# buck_converters.net
KiCad netlist of a schematic drawn in EAGLE
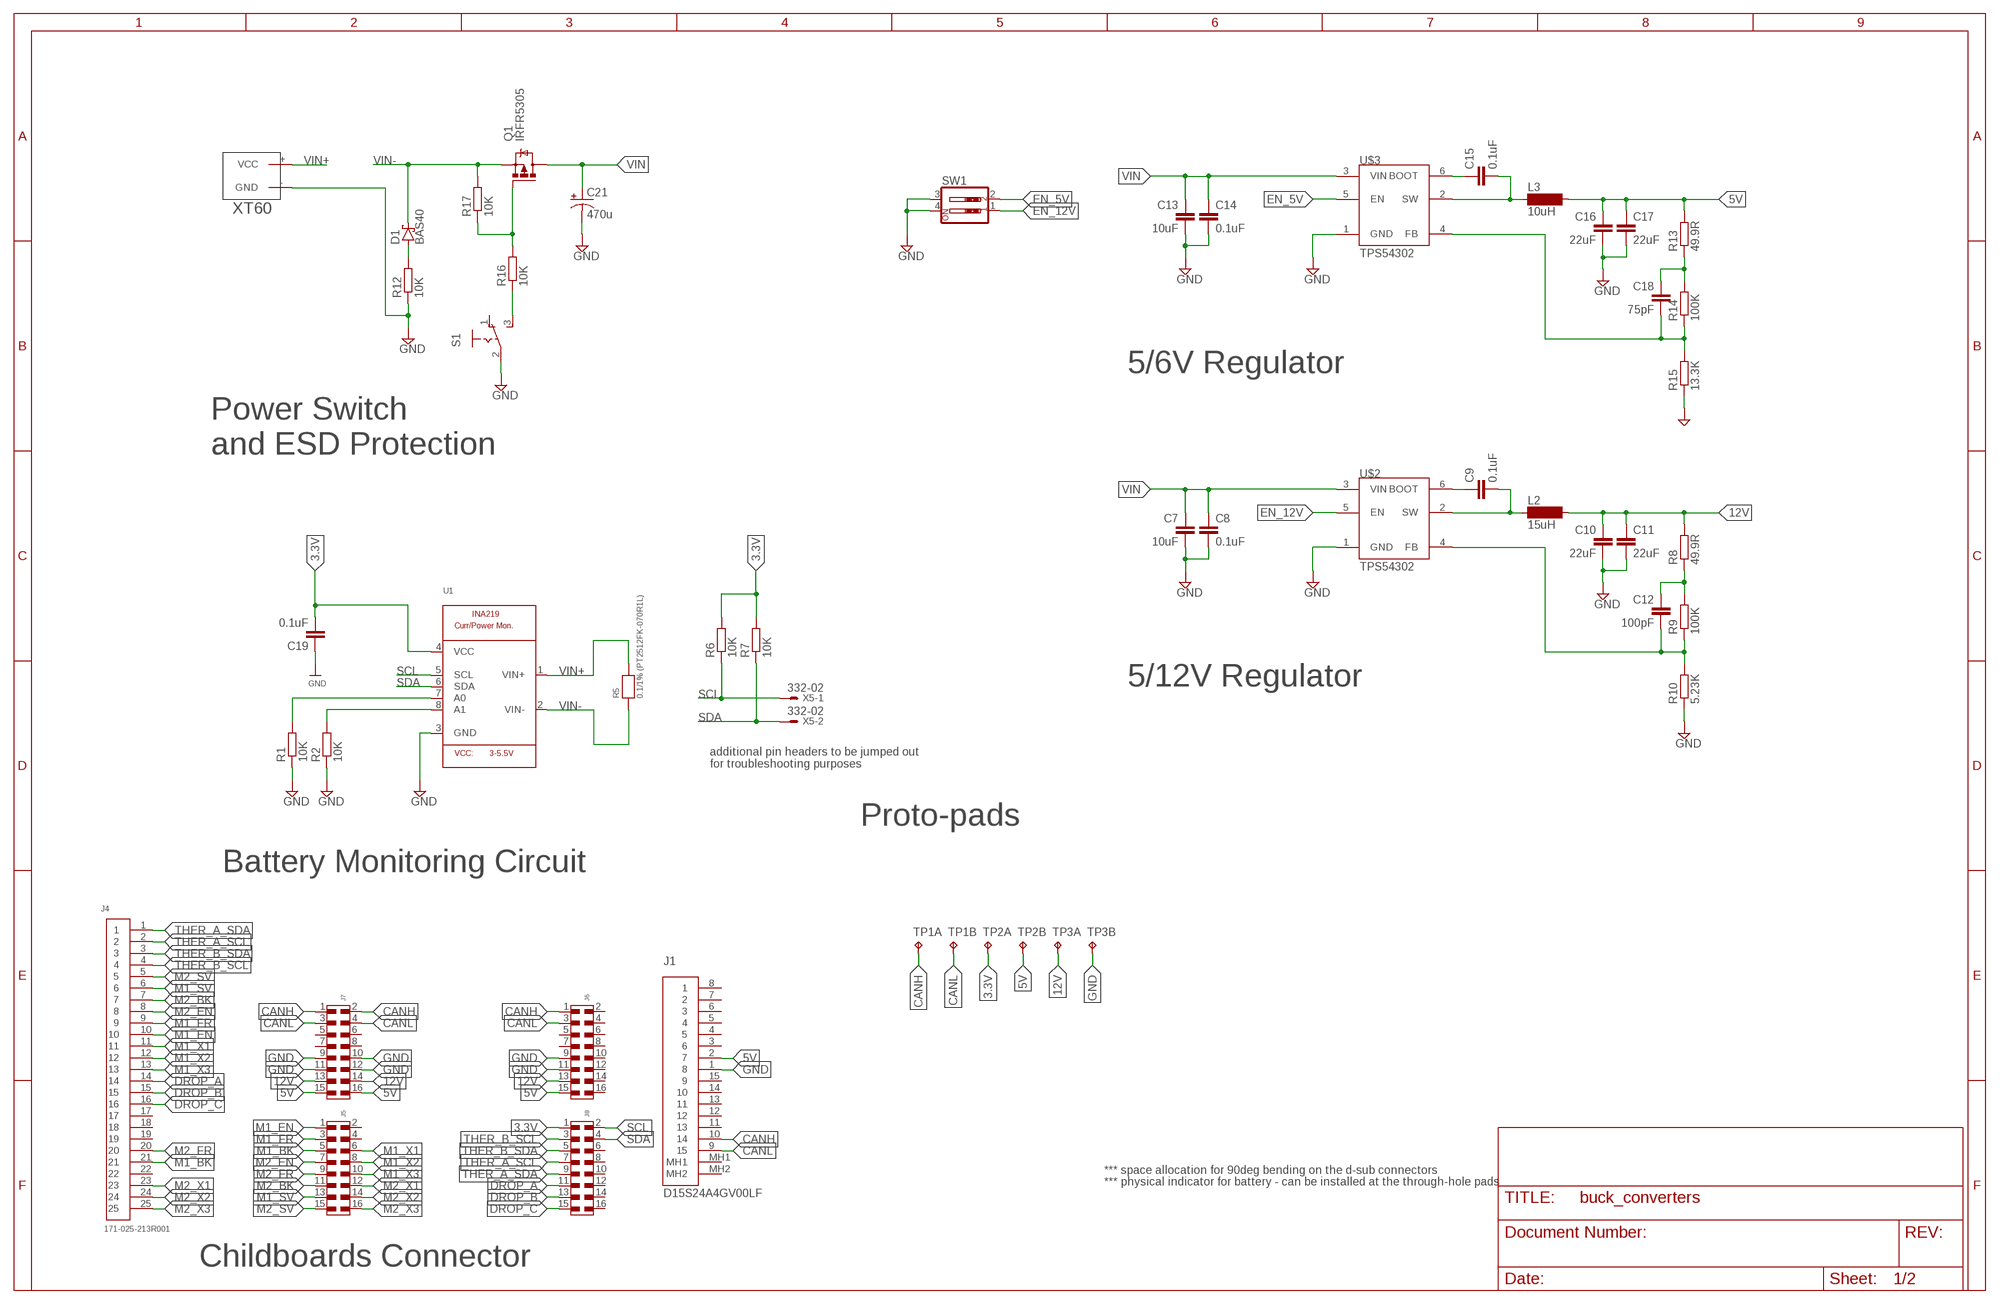
[diagram p0: schematic, sheet 1]
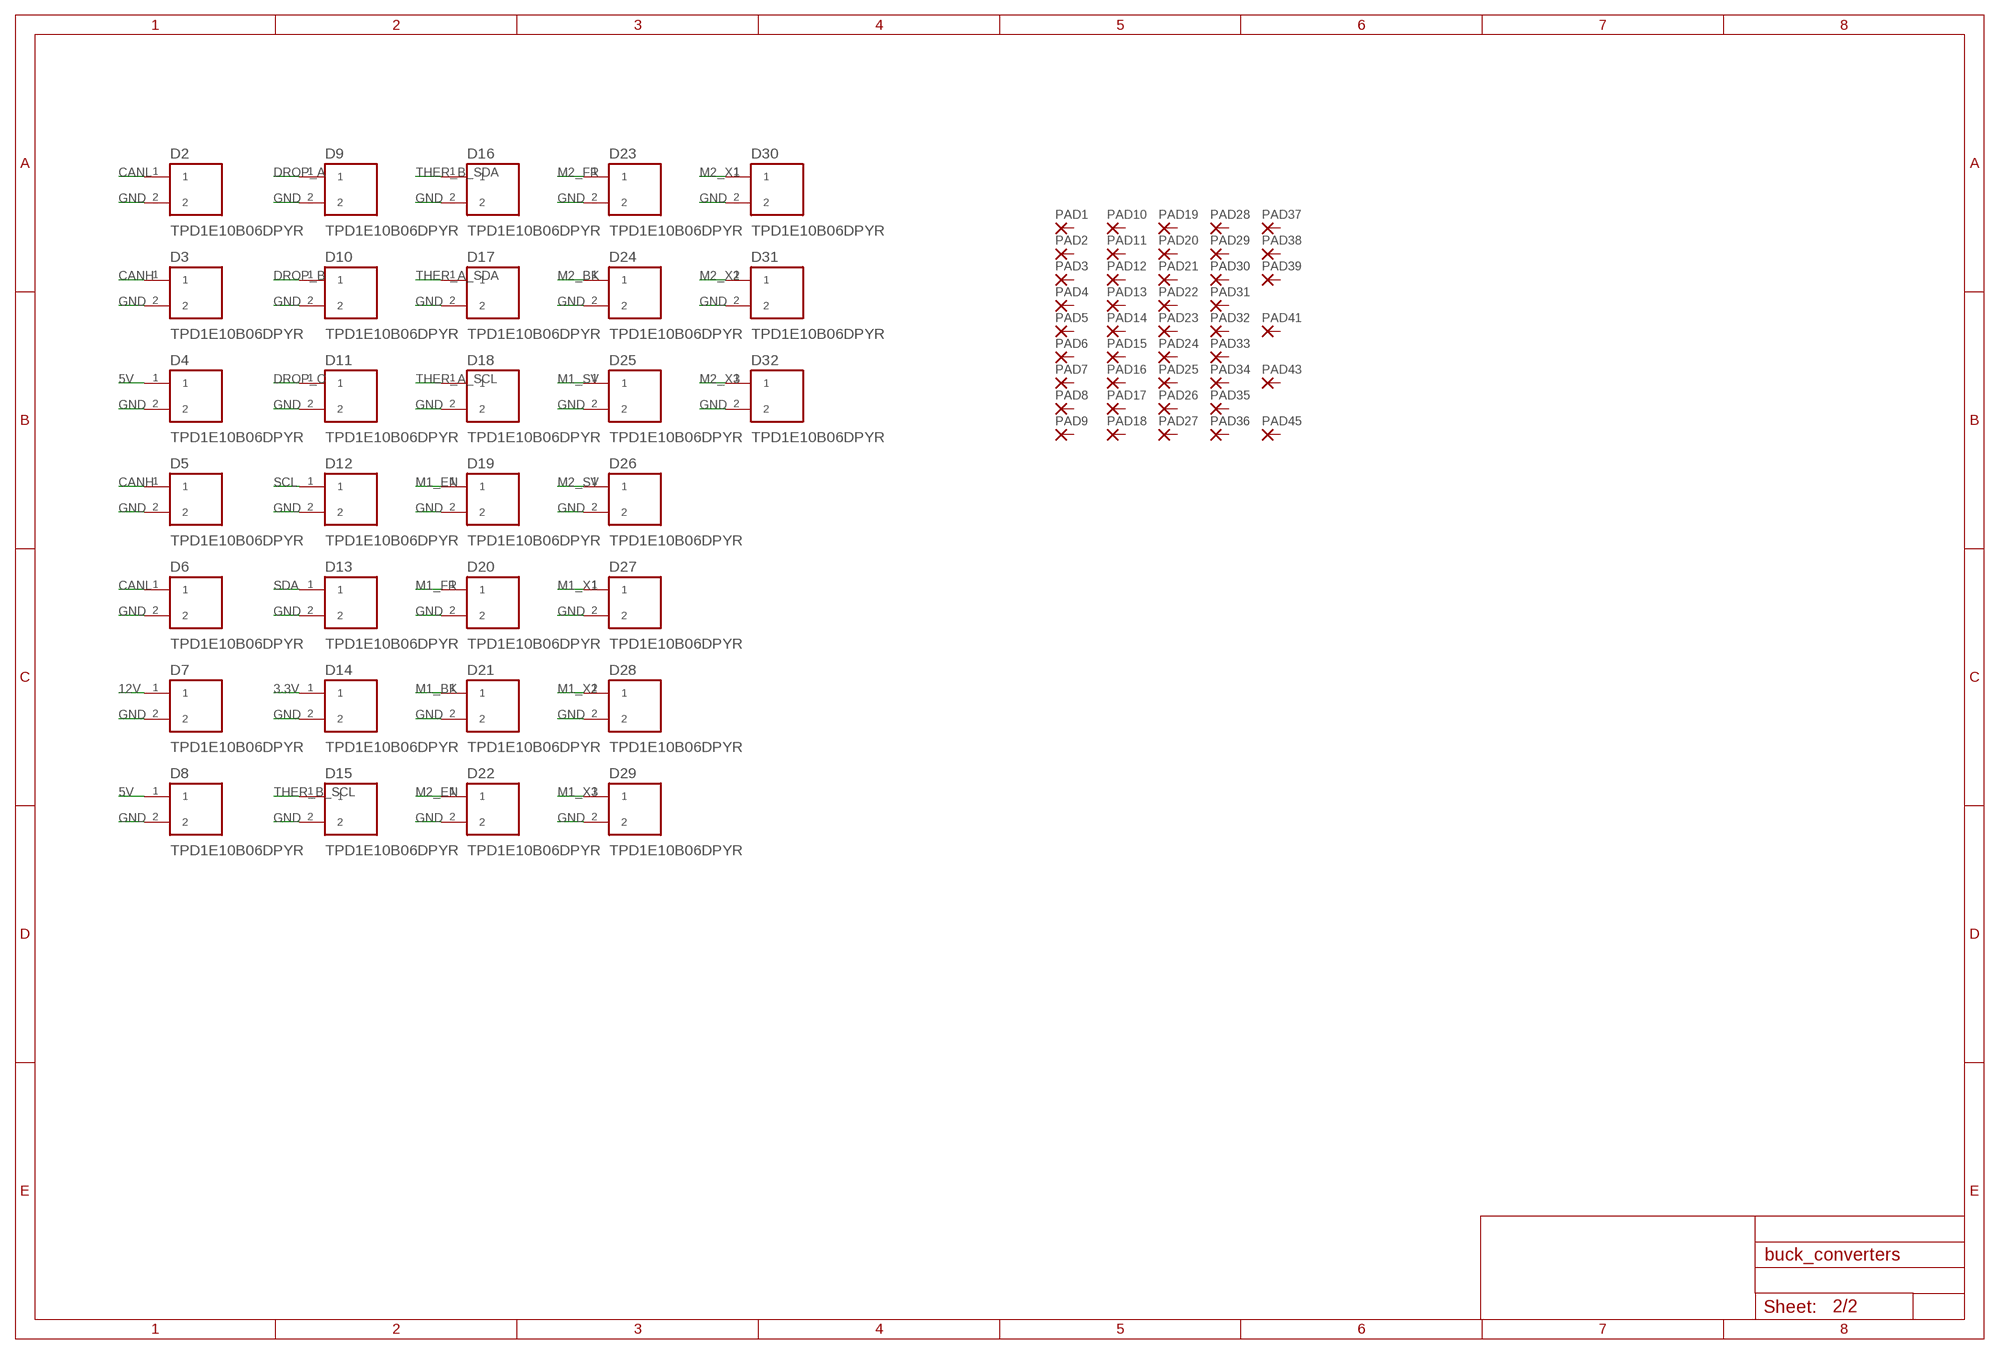
[diagram p1: schematic, sheet 2]

(export (version "E")
  (design (tool "Eeschema 10.0.6"))
  (components
    (comp (ref "C7")
      (value "10uF")
      (footprint "eagle-import:C0805")
      (libsource (lib "eagle-import") (part "C-EUC0805"))
    )
    (comp (ref "C8")
      (value "0.1uF")
      (footprint "eagle-import:C0805")
      (libsource (lib "eagle-import") (part "C-EUC0805"))
    )
    (comp (ref "C9")
      (value "0.1uF")
      (footprint "eagle-import:C0805")
      (libsource (lib "eagle-import") (part "C-EUC0805"))
    )
    (comp (ref "C10")
      (value "22uF")
      (footprint "eagle-import:C0805")
      (libsource (lib "eagle-import") (part "C-EUC0805"))
    )
    (comp (ref "C11")
      (value "22uF")
      (footprint "eagle-import:C0805")
      (libsource (lib "eagle-import") (part "C-EUC0805"))
    )
    (comp (ref "C12")
      (value "100pF")
      (footprint "eagle-import:C0805")
      (libsource (lib "eagle-import") (part "C-EUC0805"))
    )
    (comp (ref "C13")
      (value "10uF")
      (footprint "eagle-import:C0805")
      (libsource (lib "eagle-import") (part "C-EUC0805"))
    )
    (comp (ref "C14")
      (value "0.1uF")
      (footprint "eagle-import:C0805")
      (libsource (lib "eagle-import") (part "C-EUC0805"))
    )
    (comp (ref "C15")
      (value "0.1uF")
      (footprint "eagle-import:C0805")
      (libsource (lib "eagle-import") (part "C-EUC0805"))
    )
    (comp (ref "C16")
      (value "22uF")
      (footprint "eagle-import:C0805")
      (libsource (lib "eagle-import") (part "C-EUC0805"))
    )
    (comp (ref "C17")
      (value "22uF")
      (footprint "eagle-import:C0805")
      (libsource (lib "eagle-import") (part "C-EUC0805"))
    )
    (comp (ref "C18")
      (value "75pF")
      (footprint "eagle-import:C0805")
      (libsource (lib "eagle-import") (part "C-EUC0805"))
    )
    (comp (ref "C19")
      (value "0.1uF")
      (footprint "eagle-import:C0805")
      (libsource (lib "eagle-import") (part "C-EUC0805"))
    )
    (comp (ref "C21")
      (value "470u")
      (footprint "eagle-import:153CLV-1010")
      (libsource (lib "eagle-import") (part "CPOL-US153CLV-1010"))
    )
    (comp (ref "D1")
      (value "BAS40")
      (footprint "eagle-import:SOT23")
      (libsource (lib "eagle-import") (part "BAS40"))
    )
    (comp (ref "J1")
      (value "D15S24A4GV00LF")
      (footprint "eagle-import:D15S24A4GV00LF")
      (fields
        (field (name "DIGIKEY_PART_NUMBER") "609-1497-ND")
        (field (name "MANUFACTURER") "Amphenol ICC (FCI)")
        (field (name "CREATED_BY") "PCBLayout.com")
      )
      (libsource (lib "eagle-import") (part "D15S24A4GV00LF"))
    )
    (comp (ref "J4")
      (value "171-025-213R001")
      (footprint "eagle-import:171-025-213R001")
      (fields
        (field (name "DIGIKEY_PART_NO") "4225FE-ND")
        (field (name "MANUFACTURER") "NorComp Inc.")
        (field (name "CREATED_BY") "PCBLayout.com")
      )
      (libsource (lib "eagle-import") (part "171-025-213R001"))
    )
    (comp (ref "J5")
      (value "6120XX20621_61201620621")
      (footprint "eagle-import:61201620621")
      (libsource (lib "eagle-import") (part "6120XX20621_61201620621"))
    )
    (comp (ref "J6")
      (value "6120XX20621_61201620621")
      (footprint "eagle-import:61201620621")
      (libsource (lib "eagle-import") (part "6120XX20621_61201620621"))
    )
    (comp (ref "J7")
      (value "6123XX20621_61231620621")
      (footprint "eagle-import:61231620621")
      (libsource (lib "eagle-import") (part "6123XX20621_61231620621"))
    )
    (comp (ref "J8")
      (value "6120XX20621_61201620621")
      (footprint "eagle-import:61201620621")
      (libsource (lib "eagle-import") (part "6120XX20621_61201620621"))
    )
    (comp (ref "L2")
      (value "15uH")
      (footprint "eagle-import:SM-NE29")
      (libsource (lib "eagle-import") (part "SM-NE29"))
    )
    (comp (ref "L3")
      (value "10uH")
      (footprint "eagle-import:SM-NE29")
      (libsource (lib "eagle-import") (part "SM-NE29"))
    )
    (comp (ref "Q1")
      (value "IRFR5305")
      (footprint "eagle-import:D-PAK_TO252AA")
      (libsource (lib "eagle-import") (part "IRF?5305R"))
    )
    (comp (ref "R1")
      (value "10K")
      (footprint "eagle-import:R0805")
      (libsource (lib "eagle-import") (part "R-EU_R0805"))
    )
    (comp (ref "R2")
      (value "10K")
      (footprint "eagle-import:R0805")
      (libsource (lib "eagle-import") (part "R-EU_R0805"))
    )
    (comp (ref "R5")
      (value "0.1/1% (PT2512FK-070R1L)")
      (footprint "eagle-import:2512")
      (libsource (lib "eagle-import") (part "RESISTOR2512"))
    )
    (comp (ref "R6")
      (value "10K")
      (footprint "eagle-import:R0805")
      (libsource (lib "eagle-import") (part "R-EU_R0805"))
    )
    (comp (ref "R7")
      (value "10K")
      (footprint "eagle-import:R0805")
      (libsource (lib "eagle-import") (part "R-EU_R0805"))
    )
    (comp (ref "R8")
      (value "49.9R")
      (footprint "eagle-import:R0805")
      (libsource (lib "eagle-import") (part "R-EU_R0805"))
    )
    (comp (ref "R9")
      (value "100K")
      (footprint "eagle-import:R0805")
      (libsource (lib "eagle-import") (part "R-EU_R0805"))
    )
    (comp (ref "R10")
      (value "5.23K")
      (footprint "eagle-import:R0805")
      (libsource (lib "eagle-import") (part "R-EU_R0805"))
    )
    (comp (ref "R12")
      (value "10K")
      (footprint "eagle-import:R0805")
      (libsource (lib "eagle-import") (part "R-EU_R0805"))
    )
    (comp (ref "R13")
      (value "49.9R")
      (footprint "eagle-import:R0805")
      (libsource (lib "eagle-import") (part "R-EU_R0805"))
    )
    (comp (ref "R14")
      (value "100K")
      (footprint "eagle-import:R0805")
      (libsource (lib "eagle-import") (part "R-EU_R0805"))
    )
    (comp (ref "R15")
      (value "13.3K")
      (footprint "eagle-import:R0805")
      (libsource (lib "eagle-import") (part "R-EU_R0805"))
    )
    (comp (ref "R16")
      (value "10K")
      (footprint "eagle-import:R0805")
      (libsource (lib "eagle-import") (part "R-EU_R0805"))
    )
    (comp (ref "R17")
      (value "10K")
      (footprint "eagle-import:R0805")
      (libsource (lib "eagle-import") (part "R-EU_R0805"))
    )
    (comp (ref "S1")
      (value "255SB")
      (footprint "eagle-import:255SB")
      (libsource (lib "eagle-import") (part "255SB"))
    )
    (comp (ref "SW1")
      (value "SW_DIP-2")
      (footprint "eagle-import:EDG-02")
      (libsource (lib "eagle-import") (part "SW_DIP-2"))
    )
    (comp (ref "TP1")
      (value "TP2P2-38-17")
      (footprint "eagle-import:P2-38-17")
      (libsource (lib "eagle-import") (part "TP2P2-38-17"))
    )
    (comp (ref "TP2")
      (value "TP2P2-38-17")
      (footprint "eagle-import:P2-38-17")
      (libsource (lib "eagle-import") (part "TP2P2-38-17"))
    )
    (comp (ref "TP3")
      (value "TP2P2-38-17")
      (footprint "eagle-import:P2-38-17")
      (libsource (lib "eagle-import") (part "TP2P2-38-17"))
    )
    (comp (ref "U$2")
      (value "TPS54302")
      (footprint "eagle-import:SOT23-6")
      (libsource (lib "eagle-import") (part "TPS54302"))
    )
    (comp (ref "U$3")
      (value "TPS54302")
      (footprint "eagle-import:SOT23-6")
      (libsource (lib "eagle-import") (part "TPS54302"))
    )
    (comp (ref "U$9")
      (value "XT60")
      (footprint "eagle-import:XT60")
      (libsource (lib "eagle-import") (part "XT60"))
    )
    (comp (ref "U1")
      (value "INA219")
      (footprint "eagle-import:SOT23-8")
      (libsource (lib "eagle-import") (part "INA219"))
    )
    (comp (ref "X5")
      (value "332-02")
      (footprint "eagle-import:332-02")
      (libsource (lib "eagle-import") (part "332-02"))
    )
    (comp (ref "D2")
      (value "TPD1E10B06DPYR")
      (footprint "eagle-import:DIO_TPD1E05U06DPYR")
      (fields (field (name "MF") "Texas Instruments"))
      (libsource (lib "eagle-import") (part "TPD1E10B06DPYR"))
    )
    (comp (ref "D3")
      (value "TPD1E10B06DPYR")
      (footprint "eagle-import:DIO_TPD1E05U06DPYR")
      (fields (field (name "MF") "Texas Instruments"))
      (libsource (lib "eagle-import") (part "TPD1E10B06DPYR"))
    )
    (comp (ref "D4")
      (value "TPD1E10B06DPYR")
      (footprint "eagle-import:DIO_TPD1E05U06DPYR")
      (fields (field (name "MF") "Texas Instruments"))
      (libsource (lib "eagle-import") (part "TPD1E10B06DPYR"))
    )
    (comp (ref "D5")
      (value "TPD1E10B06DPYR")
      (footprint "eagle-import:DIO_TPD1E05U06DPYR")
      (fields (field (name "MF") "Texas Instruments"))
      (libsource (lib "eagle-import") (part "TPD1E10B06DPYR"))
    )
    (comp (ref "D6")
      (value "TPD1E10B06DPYR")
      (footprint "eagle-import:DIO_TPD1E05U06DPYR")
      (fields (field (name "MF") "Texas Instruments"))
      (libsource (lib "eagle-import") (part "TPD1E10B06DPYR"))
    )
    (comp (ref "D7")
      (value "TPD1E10B06DPYR")
      (footprint "eagle-import:DIO_TPD1E05U06DPYR")
      (fields (field (name "MF") "Texas Instruments"))
      (libsource (lib "eagle-import") (part "TPD1E10B06DPYR"))
    )
    (comp (ref "D8")
      (value "TPD1E10B06DPYR")
      (footprint "eagle-import:DIO_TPD1E05U06DPYR")
      (fields (field (name "MF") "Texas Instruments"))
      (libsource (lib "eagle-import") (part "TPD1E10B06DPYR"))
    )
    (comp (ref "D9")
      (value "TPD1E10B06DPYR")
      (footprint "eagle-import:DIO_TPD1E05U06DPYR")
      (fields (field (name "MF") "Texas Instruments"))
      (libsource (lib "eagle-import") (part "TPD1E10B06DPYR"))
    )
    (comp (ref "D10")
      (value "TPD1E10B06DPYR")
      (footprint "eagle-import:DIO_TPD1E05U06DPYR")
      (fields (field (name "MF") "Texas Instruments"))
      (libsource (lib "eagle-import") (part "TPD1E10B06DPYR"))
    )
    (comp (ref "D11")
      (value "TPD1E10B06DPYR")
      (footprint "eagle-import:DIO_TPD1E05U06DPYR")
      (fields (field (name "MF") "Texas Instruments"))
      (libsource (lib "eagle-import") (part "TPD1E10B06DPYR"))
    )
    (comp (ref "D12")
      (value "TPD1E10B06DPYR")
      (footprint "eagle-import:DIO_TPD1E05U06DPYR")
      (fields (field (name "MF") "Texas Instruments"))
      (libsource (lib "eagle-import") (part "TPD1E10B06DPYR"))
    )
    (comp (ref "D13")
      (value "TPD1E10B06DPYR")
      (footprint "eagle-import:DIO_TPD1E05U06DPYR")
      (fields (field (name "MF") "Texas Instruments"))
      (libsource (lib "eagle-import") (part "TPD1E10B06DPYR"))
    )
    (comp (ref "D14")
      (value "TPD1E10B06DPYR")
      (footprint "eagle-import:DIO_TPD1E05U06DPYR")
      (fields (field (name "MF") "Texas Instruments"))
      (libsource (lib "eagle-import") (part "TPD1E10B06DPYR"))
    )
    (comp (ref "D15")
      (value "TPD1E10B06DPYR")
      (footprint "eagle-import:DIO_TPD1E05U06DPYR")
      (fields (field (name "MF") "Texas Instruments"))
      (libsource (lib "eagle-import") (part "TPD1E10B06DPYR"))
    )
    (comp (ref "D16")
      (value "TPD1E10B06DPYR")
      (footprint "eagle-import:DIO_TPD1E05U06DPYR")
      (fields (field (name "MF") "Texas Instruments"))
      (libsource (lib "eagle-import") (part "TPD1E10B06DPYR"))
    )
    (comp (ref "D17")
      (value "TPD1E10B06DPYR")
      (footprint "eagle-import:DIO_TPD1E05U06DPYR")
      (fields (field (name "MF") "Texas Instruments"))
      (libsource (lib "eagle-import") (part "TPD1E10B06DPYR"))
    )
    (comp (ref "D18")
      (value "TPD1E10B06DPYR")
      (footprint "eagle-import:DIO_TPD1E05U06DPYR")
      (fields (field (name "MF") "Texas Instruments"))
      (libsource (lib "eagle-import") (part "TPD1E10B06DPYR"))
    )
    (comp (ref "D19")
      (value "TPD1E10B06DPYR")
      (footprint "eagle-import:DIO_TPD1E05U06DPYR")
      (fields (field (name "MF") "Texas Instruments"))
      (libsource (lib "eagle-import") (part "TPD1E10B06DPYR"))
    )
    (comp (ref "D20")
      (value "TPD1E10B06DPYR")
      (footprint "eagle-import:DIO_TPD1E05U06DPYR")
      (fields (field (name "MF") "Texas Instruments"))
      (libsource (lib "eagle-import") (part "TPD1E10B06DPYR"))
    )
    (comp (ref "D21")
      (value "TPD1E10B06DPYR")
      (footprint "eagle-import:DIO_TPD1E05U06DPYR")
      (fields (field (name "MF") "Texas Instruments"))
      (libsource (lib "eagle-import") (part "TPD1E10B06DPYR"))
    )
    (comp (ref "D22")
      (value "TPD1E10B06DPYR")
      (footprint "eagle-import:DIO_TPD1E05U06DPYR")
      (fields (field (name "MF") "Texas Instruments"))
      (libsource (lib "eagle-import") (part "TPD1E10B06DPYR"))
    )
    (comp (ref "D23")
      (value "TPD1E10B06DPYR")
      (footprint "eagle-import:DIO_TPD1E05U06DPYR")
      (fields (field (name "MF") "Texas Instruments"))
      (libsource (lib "eagle-import") (part "TPD1E10B06DPYR"))
    )
    (comp (ref "D24")
      (value "TPD1E10B06DPYR")
      (footprint "eagle-import:DIO_TPD1E05U06DPYR")
      (fields (field (name "MF") "Texas Instruments"))
      (libsource (lib "eagle-import") (part "TPD1E10B06DPYR"))
    )
    (comp (ref "D25")
      (value "TPD1E10B06DPYR")
      (footprint "eagle-import:DIO_TPD1E05U06DPYR")
      (fields (field (name "MF") "Texas Instruments"))
      (libsource (lib "eagle-import") (part "TPD1E10B06DPYR"))
    )
    (comp (ref "D26")
      (value "TPD1E10B06DPYR")
      (footprint "eagle-import:DIO_TPD1E05U06DPYR")
      (fields (field (name "MF") "Texas Instruments"))
      (libsource (lib "eagle-import") (part "TPD1E10B06DPYR"))
    )
    (comp (ref "D27")
      (value "TPD1E10B06DPYR")
      (footprint "eagle-import:DIO_TPD1E05U06DPYR")
      (fields (field (name "MF") "Texas Instruments"))
      (libsource (lib "eagle-import") (part "TPD1E10B06DPYR"))
    )
    (comp (ref "D28")
      (value "TPD1E10B06DPYR")
      (footprint "eagle-import:DIO_TPD1E05U06DPYR")
      (fields (field (name "MF") "Texas Instruments"))
      (libsource (lib "eagle-import") (part "TPD1E10B06DPYR"))
    )
    (comp (ref "D29")
      (value "TPD1E10B06DPYR")
      (footprint "eagle-import:DIO_TPD1E05U06DPYR")
      (fields (field (name "MF") "Texas Instruments"))
      (libsource (lib "eagle-import") (part "TPD1E10B06DPYR"))
    )
    (comp (ref "D30")
      (value "TPD1E10B06DPYR")
      (footprint "eagle-import:DIO_TPD1E05U06DPYR")
      (fields (field (name "MF") "Texas Instruments"))
      (libsource (lib "eagle-import") (part "TPD1E10B06DPYR"))
    )
    (comp (ref "D31")
      (value "TPD1E10B06DPYR")
      (footprint "eagle-import:DIO_TPD1E05U06DPYR")
      (fields (field (name "MF") "Texas Instruments"))
      (libsource (lib "eagle-import") (part "TPD1E10B06DPYR"))
    )
    (comp (ref "D32")
      (value "TPD1E10B06DPYR")
      (footprint "eagle-import:DIO_TPD1E05U06DPYR")
      (fields (field (name "MF") "Texas Instruments"))
      (libsource (lib "eagle-import") (part "TPD1E10B06DPYR"))
    )
    (comp (ref "PAD1")
      (value "2,54/1,1")
      (footprint "eagle-import:2,54_1,1")
      (libsource (lib "eagle-import") (part "2,54/1,1"))
    )
    (comp (ref "PAD2")
      (value "2,54/1,1")
      (footprint "eagle-import:2,54_1,1")
      (libsource (lib "eagle-import") (part "2,54/1,1"))
    )
    (comp (ref "PAD3")
      (value "2,54/1,1")
      (footprint "eagle-import:2,54_1,1")
      (libsource (lib "eagle-import") (part "2,54/1,1"))
    )
    (comp (ref "PAD4")
      (value "2,54/1,1")
      (footprint "eagle-import:2,54_1,1")
      (libsource (lib "eagle-import") (part "2,54/1,1"))
    )
    (comp (ref "PAD5")
      (value "2,54/1,1")
      (footprint "eagle-import:2,54_1,1")
      (libsource (lib "eagle-import") (part "2,54/1,1"))
    )
    (comp (ref "PAD6")
      (value "2,54/1,1")
      (footprint "eagle-import:2,54_1,1")
      (libsource (lib "eagle-import") (part "2,54/1,1"))
    )
    (comp (ref "PAD7")
      (value "2,54/1,1")
      (footprint "eagle-import:2,54_1,1")
      (libsource (lib "eagle-import") (part "2,54/1,1"))
    )
    (comp (ref "PAD8")
      (value "2,54/1,1")
      (footprint "eagle-import:2,54_1,1")
      (libsource (lib "eagle-import") (part "2,54/1,1"))
    )
    (comp (ref "PAD9")
      (value "2,54/1,1")
      (footprint "eagle-import:2,54_1,1")
      (libsource (lib "eagle-import") (part "2,54/1,1"))
    )
    (comp (ref "PAD10")
      (value "2,54/1,1")
      (footprint "eagle-import:2,54_1,1")
      (libsource (lib "eagle-import") (part "2,54/1,1"))
    )
    (comp (ref "PAD11")
      (value "2,54/1,1")
      (footprint "eagle-import:2,54_1,1")
      (libsource (lib "eagle-import") (part "2,54/1,1"))
    )
    (comp (ref "PAD12")
      (value "2,54/1,1")
      (footprint "eagle-import:2,54_1,1")
      (libsource (lib "eagle-import") (part "2,54/1,1"))
    )
    (comp (ref "PAD13")
      (value "2,54/1,1")
      (footprint "eagle-import:2,54_1,1")
      (libsource (lib "eagle-import") (part "2,54/1,1"))
    )
    (comp (ref "PAD14")
      (value "2,54/1,1")
      (footprint "eagle-import:2,54_1,1")
      (libsource (lib "eagle-import") (part "2,54/1,1"))
    )
    (comp (ref "PAD15")
      (value "2,54/1,1")
      (footprint "eagle-import:2,54_1,1")
      (libsource (lib "eagle-import") (part "2,54/1,1"))
    )
    (comp (ref "PAD16")
      (value "2,54/1,1")
      (footprint "eagle-import:2,54_1,1")
      (libsource (lib "eagle-import") (part "2,54/1,1"))
    )
    (comp (ref "PAD17")
      (value "2,54/1,1")
      (footprint "eagle-import:2,54_1,1")
      (libsource (lib "eagle-import") (part "2,54/1,1"))
    )
    (comp (ref "PAD18")
      (value "2,54/1,1")
      (footprint "eagle-import:2,54_1,1")
      (libsource (lib "eagle-import") (part "2,54/1,1"))
    )
    (comp (ref "PAD19")
      (value "2,54/1,1")
      (footprint "eagle-import:2,54_1,1")
      (libsource (lib "eagle-import") (part "2,54/1,1"))
    )
    (comp (ref "PAD20")
      (value "2,54/1,1")
      (footprint "eagle-import:2,54_1,1")
      (libsource (lib "eagle-import") (part "2,54/1,1"))
    )
    (comp (ref "PAD21")
      (value "2,54/1,1")
      (footprint "eagle-import:2,54_1,1")
      (libsource (lib "eagle-import") (part "2,54/1,1"))
    )
    (comp (ref "PAD22")
      (value "2,54/1,1")
      (footprint "eagle-import:2,54_1,1")
      (libsource (lib "eagle-import") (part "2,54/1,1"))
    )
    (comp (ref "PAD23")
      (value "2,54/1,1")
      (footprint "eagle-import:2,54_1,1")
      (libsource (lib "eagle-import") (part "2,54/1,1"))
    )
    (comp (ref "PAD24")
      (value "2,54/1,1")
      (footprint "eagle-import:2,54_1,1")
      (libsource (lib "eagle-import") (part "2,54/1,1"))
    )
    (comp (ref "PAD25")
      (value "2,54/1,1")
      (footprint "eagle-import:2,54_1,1")
      (libsource (lib "eagle-import") (part "2,54/1,1"))
    )
    (comp (ref "PAD26")
      (value "2,54/1,1")
      (footprint "eagle-import:2,54_1,1")
      (libsource (lib "eagle-import") (part "2,54/1,1"))
    )
    (comp (ref "PAD27")
      (value "2,54/1,1")
      (footprint "eagle-import:2,54_1,1")
      (libsource (lib "eagle-import") (part "2,54/1,1"))
    )
    (comp (ref "PAD28")
      (value "2,54/1,1")
      (footprint "eagle-import:2,54_1,1")
      (libsource (lib "eagle-import") (part "2,54/1,1"))
    )
    (comp (ref "PAD29")
      (value "2,54/1,1")
      (footprint "eagle-import:2,54_1,1")
      (libsource (lib "eagle-import") (part "2,54/1,1"))
    )
    (comp (ref "PAD30")
      (value "2,54/1,1")
      (footprint "eagle-import:2,54_1,1")
      (libsource (lib "eagle-import") (part "2,54/1,1"))
    )
    (comp (ref "PAD31")
      (value "2,54/1,1")
      (footprint "eagle-import:2,54_1,1")
      (libsource (lib "eagle-import") (part "2,54/1,1"))
    )
    (comp (ref "PAD32")
      (value "2,54/1,1")
      (footprint "eagle-import:2,54_1,1")
      (libsource (lib "eagle-import") (part "2,54/1,1"))
    )
    (comp (ref "PAD33")
      (value "2,54/1,1")
      (footprint "eagle-import:2,54_1,1")
      (libsource (lib "eagle-import") (part "2,54/1,1"))
    )
    (comp (ref "PAD34")
      (value "2,54/1,1")
      (footprint "eagle-import:2,54_1,1")
      (libsource (lib "eagle-import") (part "2,54/1,1"))
    )
    (comp (ref "PAD35")
      (value "2,54/1,1")
      (footprint "eagle-import:2,54_1,1")
      (libsource (lib "eagle-import") (part "2,54/1,1"))
    )
    (comp (ref "PAD36")
      (value "2,54/1,1")
      (footprint "eagle-import:2,54_1,1")
      (libsource (lib "eagle-import") (part "2,54/1,1"))
    )
    (comp (ref "PAD37")
      (value "2,54/1,1")
      (footprint "eagle-import:2,54_1,1")
      (libsource (lib "eagle-import") (part "2,54/1,1"))
    )
    (comp (ref "PAD38")
      (value "2,54/1,1")
      (footprint "eagle-import:2,54_1,1")
      (libsource (lib "eagle-import") (part "2,54/1,1"))
    )
    (comp (ref "PAD39")
      (value "2,54/1,1")
      (footprint "eagle-import:2,54_1,1")
      (libsource (lib "eagle-import") (part "2,54/1,1"))
    )
    (comp (ref "PAD41")
      (value "2,54/1,1")
      (footprint "eagle-import:2,54_1,1")
      (libsource (lib "eagle-import") (part "2,54/1,1"))
    )
    (comp (ref "PAD43")
      (value "2,54/1,1")
      (footprint "eagle-import:2,54_1,1")
      (libsource (lib "eagle-import") (part "2,54/1,1"))
    )
    (comp (ref "PAD45")
      (value "2,54/1,1")
      (footprint "eagle-import:2,54_1,1")
      (libsource (lib "eagle-import") (part "2,54/1,1"))
    )
  )
  (nets
    (net (code "1") (name "3.3V") (class "Default")
      (node (ref "C19") (pin "2") (pinfunction "2_2") (pintype "passive"))
      (node (ref "D14") (pin "1") (pinfunction "1_1") (pintype "bidirectional"))
      (node (ref "J8") (pin "1") (pinfunction "1_1") (pintype "passive"))
      (node (ref "R6") (pin "2") (pinfunction "2_2") (pintype "passive"))
      (node (ref "R7") (pin "2") (pinfunction "2_2") (pintype "passive"))
      (node (ref "TP2") (pin "TP-1") (pinfunction "TP_TP-1") (pintype "input"))
      (node (ref "U1") (pin "4") (pinfunction "VCC_4") (pintype "bidirectional"))
    )
    (net (code "2") (name "5V") (class "Default")
      (node (ref "C16") (pin "1") (pinfunction "1_1") (pintype "passive"))
      (node (ref "C17") (pin "1") (pinfunction "1_1") (pintype "passive"))
      (node (ref "D4") (pin "1") (pinfunction "1_1") (pintype "bidirectional"))
      (node (ref "D8") (pin "1") (pinfunction "1_1") (pintype "bidirectional"))
      (node (ref "J1") (pin "2") (pinfunction "7_2") (pintype "passive"))
      (node (ref "J6") (pin "15") (pinfunction "15_15") (pintype "passive"))
      (node (ref "J7") (pin "15") (pinfunction "15_15") (pintype "passive"))
      (node (ref "J7") (pin "16") (pinfunction "16_16") (pintype "passive"))
      (node (ref "L3") (pin "2") (pinfunction "2_2") (pintype "passive"))
      (node (ref "R13") (pin "2") (pinfunction "2_2") (pintype "passive"))
      (node (ref "TP2") (pin "TP-2") (pinfunction "TP_TP-2") (pintype "input"))
    )
    (net (code "3") (name "12V") (class "Default")
      (node (ref "C10") (pin "1") (pinfunction "1_1") (pintype "passive"))
      (node (ref "C11") (pin "1") (pinfunction "1_1") (pintype "passive"))
      (node (ref "D7") (pin "1") (pinfunction "1_1") (pintype "bidirectional"))
      (node (ref "J6") (pin "13") (pinfunction "13_13") (pintype "passive"))
      (node (ref "J7") (pin "13") (pinfunction "13_13") (pintype "passive"))
      (node (ref "J7") (pin "14") (pinfunction "14_14") (pintype "passive"))
      (node (ref "L2") (pin "2") (pinfunction "2_2") (pintype "passive"))
      (node (ref "R8") (pin "2") (pinfunction "2_2") (pintype "passive"))
      (node (ref "TP3") (pin "TP-1") (pinfunction "TP_TP-1") (pintype "input"))
    )
    (net (code "4") (name "CANH") (class "Default")
      (node (ref "D3") (pin "1") (pinfunction "1_1") (pintype "bidirectional"))
      (node (ref "D5") (pin "1") (pinfunction "1_1") (pintype "bidirectional"))
      (node (ref "J1") (pin "10") (pinfunction "14_10") (pintype "passive"))
      (node (ref "J6") (pin "1") (pinfunction "1_1") (pintype "passive"))
      (node (ref "J7") (pin "1") (pinfunction "1_1") (pintype "passive"))
      (node (ref "J7") (pin "2") (pinfunction "2_2") (pintype "passive"))
      (node (ref "TP1") (pin "TP-1") (pinfunction "TP_TP-1") (pintype "input"))
    )
    (net (code "5") (name "CANL") (class "Default")
      (node (ref "D2") (pin "1") (pinfunction "1_1") (pintype "bidirectional"))
      (node (ref "D6") (pin "1") (pinfunction "1_1") (pintype "bidirectional"))
      (node (ref "J1") (pin "9") (pinfunction "15_9") (pintype "passive"))
      (node (ref "J6") (pin "3") (pinfunction "3_3") (pintype "passive"))
      (node (ref "J7") (pin "3") (pinfunction "3_3") (pintype "passive"))
      (node (ref "J7") (pin "4") (pinfunction "4_4") (pintype "passive"))
      (node (ref "TP1") (pin "TP-2") (pinfunction "TP_TP-2") (pintype "input"))
    )
    (net (code "6") (name "DROP_A") (class "Default")
      (node (ref "D9") (pin "1") (pinfunction "1_1") (pintype "bidirectional"))
      (node (ref "J4") (pin "14") (pinfunction "14_14") (pintype "passive"))
      (node (ref "J8") (pin "11") (pinfunction "11_11") (pintype "passive"))
    )
    (net (code "7") (name "DROP_B") (class "Default")
      (node (ref "D10") (pin "1") (pinfunction "1_1") (pintype "bidirectional"))
      (node (ref "J4") (pin "15") (pinfunction "15_15") (pintype "passive"))
      (node (ref "J8") (pin "13") (pinfunction "13_13") (pintype "passive"))
    )
    (net (code "8") (name "DROP_C") (class "Default")
      (node (ref "D11") (pin "1") (pinfunction "1_1") (pintype "bidirectional"))
      (node (ref "J4") (pin "16") (pinfunction "16_16") (pintype "passive"))
      (node (ref "J8") (pin "15") (pinfunction "15_15") (pintype "passive"))
    )
    (net (code "9") (name "EN_5V") (class "Default")
      (node (ref "SW1") (pin "2") (pinfunction "2_2") (pintype "passive"))
      (node (ref "U$3") (pin "5") (pinfunction "EN_5") (pintype "bidirectional"))
    )
    (net (code "10") (name "EN_12V") (class "Default")
      (node (ref "SW1") (pin "1") (pinfunction "1_1") (pintype "passive"))
      (node (ref "U$2") (pin "5") (pinfunction "EN_5") (pintype "bidirectional"))
    )
    (net (code "11") (name "GND") (class "Default")
      (node (ref "C10") (pin "2") (pinfunction "2_2") (pintype "passive"))
      (node (ref "C11") (pin "2") (pinfunction "2_2") (pintype "passive"))
      (node (ref "C13") (pin "2") (pinfunction "2_2") (pintype "passive"))
      (node (ref "C14") (pin "2") (pinfunction "2_2") (pintype "passive"))
      (node (ref "C16") (pin "2") (pinfunction "2_2") (pintype "passive"))
      (node (ref "C17") (pin "2") (pinfunction "2_2") (pintype "passive"))
      (node (ref "C19") (pin "1") (pinfunction "1_1") (pintype "passive"))
      (node (ref "C21") (pin "-") (pinfunction "-_-") (pintype "passive"))
      (node (ref "C7") (pin "2") (pinfunction "2_2") (pintype "passive"))
      (node (ref "C8") (pin "2") (pinfunction "2_2") (pintype "passive"))
      (node (ref "D10") (pin "2") (pinfunction "2_2") (pintype "bidirectional"))
      (node (ref "D11") (pin "2") (pinfunction "2_2") (pintype "bidirectional"))
      (node (ref "D12") (pin "2") (pinfunction "2_2") (pintype "bidirectional"))
      (node (ref "D13") (pin "2") (pinfunction "2_2") (pintype "bidirectional"))
      (node (ref "D14") (pin "2") (pinfunction "2_2") (pintype "bidirectional"))
      (node (ref "D15") (pin "2") (pinfunction "2_2") (pintype "bidirectional"))
      (node (ref "D16") (pin "2") (pinfunction "2_2") (pintype "bidirectional"))
      (node (ref "D17") (pin "2") (pinfunction "2_2") (pintype "bidirectional"))
      (node (ref "D18") (pin "2") (pinfunction "2_2") (pintype "bidirectional"))
      (node (ref "D19") (pin "2") (pinfunction "2_2") (pintype "bidirectional"))
      (node (ref "D2") (pin "2") (pinfunction "2_2") (pintype "bidirectional"))
      (node (ref "D20") (pin "2") (pinfunction "2_2") (pintype "bidirectional"))
      (node (ref "D21") (pin "2") (pinfunction "2_2") (pintype "bidirectional"))
      (node (ref "D22") (pin "2") (pinfunction "2_2") (pintype "bidirectional"))
      (node (ref "D23") (pin "2") (pinfunction "2_2") (pintype "bidirectional"))
      (node (ref "D24") (pin "2") (pinfunction "2_2") (pintype "bidirectional"))
      (node (ref "D25") (pin "2") (pinfunction "2_2") (pintype "bidirectional"))
      (node (ref "D26") (pin "2") (pinfunction "2_2") (pintype "bidirectional"))
      (node (ref "D27") (pin "2") (pinfunction "2_2") (pintype "bidirectional"))
      (node (ref "D28") (pin "2") (pinfunction "2_2") (pintype "bidirectional"))
      (node (ref "D29") (pin "2") (pinfunction "2_2") (pintype "bidirectional"))
      (node (ref "D3") (pin "2") (pinfunction "2_2") (pintype "bidirectional"))
      (node (ref "D30") (pin "2") (pinfunction "2_2") (pintype "bidirectional"))
      (node (ref "D31") (pin "2") (pinfunction "2_2") (pintype "bidirectional"))
      (node (ref "D32") (pin "2") (pinfunction "2_2") (pintype "bidirectional"))
      (node (ref "D4") (pin "2") (pinfunction "2_2") (pintype "bidirectional"))
      (node (ref "D5") (pin "2") (pinfunction "2_2") (pintype "bidirectional"))
      (node (ref "D6") (pin "2") (pinfunction "2_2") (pintype "bidirectional"))
      (node (ref "D7") (pin "2") (pinfunction "2_2") (pintype "bidirectional"))
      (node (ref "D8") (pin "2") (pinfunction "2_2") (pintype "bidirectional"))
      (node (ref "D9") (pin "2") (pinfunction "2_2") (pintype "bidirectional"))
      (node (ref "J1") (pin "1") (pinfunction "8_1") (pintype "passive"))
      (node (ref "J6") (pin "11") (pinfunction "11_11") (pintype "passive"))
      (node (ref "J6") (pin "9") (pinfunction "9_9") (pintype "passive"))
      (node (ref "J7") (pin "10") (pinfunction "10_10") (pintype "passive"))
      (node (ref "J7") (pin "11") (pinfunction "11_11") (pintype "passive"))
      (node (ref "J7") (pin "12") (pinfunction "12_12") (pintype "passive"))
      (node (ref "J7") (pin "9") (pinfunction "9_9") (pintype "passive"))
      (node (ref "R1") (pin "1") (pinfunction "1_1") (pintype "passive"))
      (node (ref "R10") (pin "1") (pinfunction "1_1") (pintype "passive"))
      (node (ref "R12") (pin "1") (pinfunction "1_1") (pintype "passive"))
      (node (ref "R15") (pin "1") (pinfunction "1_1") (pintype "passive"))
      (node (ref "R2") (pin "1") (pinfunction "1_1") (pintype "passive"))
      (node (ref "S1") (pin "2") (pinfunction "P_2") (pintype "passive"))
      (node (ref "SW1") (pin "3") (pinfunction "3_3") (pintype "passive"))
      (node (ref "SW1") (pin "4") (pinfunction "4_4") (pintype "passive"))
      (node (ref "TP3") (pin "TP-2") (pinfunction "TP_TP-2") (pintype "input"))
      (node (ref "U$2") (pin "1") (pinfunction "GND_1") (pintype "bidirectional"))
      (node (ref "U$3") (pin "1") (pinfunction "GND_1") (pintype "bidirectional"))
      (node (ref "U$9") (pin "-") (pinfunction "GND_-") (pintype "bidirectional"))
      (node (ref "U1") (pin "3") (pinfunction "GND_3") (pintype "bidirectional"))
    )
    (net (code "12") (name "M1_BK") (class "Default")
      (node (ref "D21") (pin "1") (pinfunction "1_1") (pintype "bidirectional"))
      (node (ref "J4") (pin "21") (pinfunction "21_21") (pintype "passive"))
      (node (ref "J5") (pin "5") (pinfunction "5_5") (pintype "passive"))
    )
    (net (code "13") (name "M1_EN") (class "Default")
      (node (ref "D19") (pin "1") (pinfunction "1_1") (pintype "bidirectional"))
      (node (ref "J4") (pin "10") (pinfunction "10_10") (pintype "passive"))
      (node (ref "J5") (pin "1") (pinfunction "1_1") (pintype "passive"))
    )
    (net (code "14") (name "M1_FR") (class "Default")
      (node (ref "D20") (pin "1") (pinfunction "1_1") (pintype "bidirectional"))
      (node (ref "J4") (pin "9") (pinfunction "9_9") (pintype "passive"))
      (node (ref "J5") (pin "3") (pinfunction "3_3") (pintype "passive"))
    )
    (net (code "15") (name "M1_SV") (class "Default")
      (node (ref "D25") (pin "1") (pinfunction "1_1") (pintype "bidirectional"))
      (node (ref "J4") (pin "6") (pinfunction "6_6") (pintype "passive"))
      (node (ref "J5") (pin "13") (pinfunction "13_13") (pintype "passive"))
    )
    (net (code "16") (name "M1_X1") (class "Default")
      (node (ref "D27") (pin "1") (pinfunction "1_1") (pintype "bidirectional"))
      (node (ref "J4") (pin "11") (pinfunction "11_11") (pintype "passive"))
      (node (ref "J5") (pin "6") (pinfunction "6_6") (pintype "passive"))
    )
    (net (code "17") (name "M1_X2") (class "Default")
      (node (ref "D28") (pin "1") (pinfunction "1_1") (pintype "bidirectional"))
      (node (ref "J4") (pin "12") (pinfunction "12_12") (pintype "passive"))
      (node (ref "J5") (pin "8") (pinfunction "8_8") (pintype "passive"))
    )
    (net (code "18") (name "M1_X3") (class "Default")
      (node (ref "D29") (pin "1") (pinfunction "1_1") (pintype "bidirectional"))
      (node (ref "J4") (pin "13") (pinfunction "13_13") (pintype "passive"))
      (node (ref "J5") (pin "10") (pinfunction "10_10") (pintype "passive"))
    )
    (net (code "19") (name "M2_BK") (class "Default")
      (node (ref "D24") (pin "1") (pinfunction "1_1") (pintype "bidirectional"))
      (node (ref "J4") (pin "7") (pinfunction "7_7") (pintype "passive"))
      (node (ref "J5") (pin "11") (pinfunction "11_11") (pintype "passive"))
    )
    (net (code "20") (name "M2_EN") (class "Default")
      (node (ref "D22") (pin "1") (pinfunction "1_1") (pintype "bidirectional"))
      (node (ref "J4") (pin "8") (pinfunction "8_8") (pintype "passive"))
      (node (ref "J5") (pin "7") (pinfunction "7_7") (pintype "passive"))
    )
    (net (code "21") (name "M2_FR") (class "Default")
      (node (ref "D23") (pin "1") (pinfunction "1_1") (pintype "bidirectional"))
      (node (ref "J4") (pin "20") (pinfunction "20_20") (pintype "passive"))
      (node (ref "J5") (pin "9") (pinfunction "9_9") (pintype "passive"))
    )
    (net (code "22") (name "M2_SV") (class "Default")
      (node (ref "D26") (pin "1") (pinfunction "1_1") (pintype "bidirectional"))
      (node (ref "J4") (pin "5") (pinfunction "5_5") (pintype "passive"))
      (node (ref "J5") (pin "15") (pinfunction "15_15") (pintype "passive"))
    )
    (net (code "23") (name "M2_X1") (class "Default")
      (node (ref "D30") (pin "1") (pinfunction "1_1") (pintype "bidirectional"))
      (node (ref "J4") (pin "23") (pinfunction "23_23") (pintype "passive"))
      (node (ref "J5") (pin "12") (pinfunction "12_12") (pintype "passive"))
    )
    (net (code "24") (name "M2_X2") (class "Default")
      (node (ref "D31") (pin "1") (pinfunction "1_1") (pintype "bidirectional"))
      (node (ref "J4") (pin "24") (pinfunction "24_24") (pintype "passive"))
      (node (ref "J5") (pin "14") (pinfunction "14_14") (pintype "passive"))
    )
    (net (code "25") (name "M2_X3") (class "Default")
      (node (ref "D32") (pin "1") (pinfunction "1_1") (pintype "bidirectional"))
      (node (ref "J4") (pin "25") (pinfunction "25_25") (pintype "passive"))
      (node (ref "J5") (pin "16") (pinfunction "16_16") (pintype "passive"))
    )
    (net (code "26") (name "Net-(C12-Pad1)") (class "Default")
      (node (ref "C12") (pin "1") (pinfunction "1_1") (pintype "passive"))
      (node (ref "R8") (pin "1") (pinfunction "1_1") (pintype "passive"))
      (node (ref "R9") (pin "2") (pinfunction "2_2") (pintype "passive"))
    )
    (net (code "27") (name "Net-(C18-Pad1)") (class "Default")
      (node (ref "C18") (pin "1") (pinfunction "1_1") (pintype "passive"))
      (node (ref "R13") (pin "1") (pinfunction "1_1") (pintype "passive"))
      (node (ref "R14") (pin "2") (pinfunction "2_2") (pintype "passive"))
    )
    (net (code "28") (name "Net-(D1-A)") (class "Default")
      (node (ref "D1") (pin "1") (pinfunction "A_1") (pintype "passive"))
      (node (ref "R12") (pin "2") (pinfunction "2_2") (pintype "passive"))
    )
    (net (code "29") (name "Net-(Q1-G)") (class "Default")
      (node (ref "Q1") (pin "1") (pinfunction "G_1") (pintype "passive"))
      (node (ref "R16") (pin "2") (pinfunction "2_2") (pintype "passive"))
      (node (ref "R17") (pin "1") (pinfunction "1_1") (pintype "passive"))
    )
    (net (code "30") (name "Net-(S1-S)") (class "Default")
      (node (ref "R16") (pin "1") (pinfunction "1_1") (pintype "passive"))
      (node (ref "S1") (pin "3") (pinfunction "S_3") (pintype "passive"))
    )
    (net (code "31") (name "Net-(U$2-BOOT)") (class "Default")
      (node (ref "C9") (pin "1") (pinfunction "1_1") (pintype "passive"))
      (node (ref "U$2") (pin "6") (pinfunction "BOOT_6") (pintype "bidirectional"))
    )
    (net (code "32") (name "Net-(U$2-FB)") (class "Default")
      (node (ref "C12") (pin "2") (pinfunction "2_2") (pintype "passive"))
      (node (ref "R10") (pin "2") (pinfunction "2_2") (pintype "passive"))
      (node (ref "R9") (pin "1") (pinfunction "1_1") (pintype "passive"))
      (node (ref "U$2") (pin "4") (pinfunction "FB_4") (pintype "bidirectional"))
    )
    (net (code "33") (name "Net-(U$2-SW)") (class "Default")
      (node (ref "C9") (pin "2") (pinfunction "2_2") (pintype "passive"))
      (node (ref "L2") (pin "1") (pinfunction "1_1") (pintype "passive"))
      (node (ref "U$2") (pin "2") (pinfunction "SW_2") (pintype "bidirectional"))
    )
    (net (code "34") (name "Net-(U$3-BOOT)") (class "Default")
      (node (ref "C15") (pin "1") (pinfunction "1_1") (pintype "passive"))
      (node (ref "U$3") (pin "6") (pinfunction "BOOT_6") (pintype "bidirectional"))
    )
    (net (code "35") (name "Net-(U$3-FB)") (class "Default")
      (node (ref "C18") (pin "2") (pinfunction "2_2") (pintype "passive"))
      (node (ref "R14") (pin "1") (pinfunction "1_1") (pintype "passive"))
      (node (ref "R15") (pin "2") (pinfunction "2_2") (pintype "passive"))
      (node (ref "U$3") (pin "4") (pinfunction "FB_4") (pintype "bidirectional"))
    )
    (net (code "36") (name "Net-(U$3-SW)") (class "Default")
      (node (ref "C15") (pin "2") (pinfunction "2_2") (pintype "passive"))
      (node (ref "L3") (pin "1") (pinfunction "1_1") (pintype "passive"))
      (node (ref "U$3") (pin "2") (pinfunction "SW_2") (pintype "bidirectional"))
    )
    (net (code "37") (name "Net-(U1-A0)") (class "Default")
      (node (ref "R1") (pin "2") (pinfunction "2_2") (pintype "passive"))
      (node (ref "U1") (pin "7") (pinfunction "A0_7") (pintype "bidirectional"))
    )
    (net (code "38") (name "Net-(U1-A1)") (class "Default")
      (node (ref "R2") (pin "2") (pinfunction "2_2") (pintype "passive"))
      (node (ref "U1") (pin "8") (pinfunction "A1_8") (pintype "bidirectional"))
    )
    (net (code "39") (name "SCL") (class "Default")
      (node (ref "D12") (pin "1") (pinfunction "1_1") (pintype "bidirectional"))
      (node (ref "J8") (pin "2") (pinfunction "2_2") (pintype "passive"))
      (node (ref "R6") (pin "1") (pinfunction "1_1") (pintype "passive"))
      (node (ref "U1") (pin "5") (pinfunction "SCL_5") (pintype "bidirectional"))
      (node (ref "X5") (pin "1") (pinfunction "S_1") (pintype "passive"))
    )
    (net (code "40") (name "SDA") (class "Default")
      (node (ref "D13") (pin "1") (pinfunction "1_1") (pintype "bidirectional"))
      (node (ref "J8") (pin "4") (pinfunction "4_4") (pintype "passive"))
      (node (ref "R7") (pin "1") (pinfunction "1_1") (pintype "passive"))
      (node (ref "U1") (pin "6") (pinfunction "SDA_6") (pintype "bidirectional"))
      (node (ref "X5") (pin "2") (pinfunction "S_2") (pintype "passive"))
    )
    (net (code "41") (name "THER_A_SCL") (class "Default")
      (node (ref "D18") (pin "1") (pinfunction "1_1") (pintype "bidirectional"))
      (node (ref "J4") (pin "2") (pinfunction "2_2") (pintype "passive"))
      (node (ref "J8") (pin "7") (pinfunction "7_7") (pintype "passive"))
    )
    (net (code "42") (name "THER_A_SDA") (class "Default")
      (node (ref "D17") (pin "1") (pinfunction "1_1") (pintype "bidirectional"))
      (node (ref "J4") (pin "1") (pinfunction "1_1") (pintype "passive"))
      (node (ref "J8") (pin "9") (pinfunction "9_9") (pintype "passive"))
    )
    (net (code "43") (name "THER_B_SCL") (class "Default")
      (node (ref "D15") (pin "1") (pinfunction "1_1") (pintype "bidirectional"))
      (node (ref "J4") (pin "4") (pinfunction "4_4") (pintype "passive"))
      (node (ref "J8") (pin "3") (pinfunction "3_3") (pintype "passive"))
    )
    (net (code "44") (name "THER_B_SDA") (class "Default")
      (node (ref "D16") (pin "1") (pinfunction "1_1") (pintype "bidirectional"))
      (node (ref "J4") (pin "3") (pinfunction "3_3") (pintype "passive"))
      (node (ref "J8") (pin "5") (pinfunction "5_5") (pintype "passive"))
    )
    (net (code "45") (name "VIN") (class "Default")
      (node (ref "C13") (pin "1") (pinfunction "1_1") (pintype "passive"))
      (node (ref "C14") (pin "1") (pinfunction "1_1") (pintype "passive"))
      (node (ref "C21") (pin "+") (pinfunction "+_+") (pintype "passive"))
      (node (ref "C7") (pin "1") (pinfunction "1_1") (pintype "passive"))
      (node (ref "C8") (pin "1") (pinfunction "1_1") (pintype "passive"))
      (node (ref "Q1") (pin "4") (pinfunction "D_4") (pintype "passive"))
      (node (ref "U$2") (pin "3") (pinfunction "VIN_3") (pintype "bidirectional"))
      (node (ref "U$3") (pin "3") (pinfunction "VIN_3") (pintype "bidirectional"))
    )
    (net (code "46") (name "VIN+") (class "Default")
      (node (ref "R5") (pin "2") (pinfunction "2_2") (pintype "passive"))
      (node (ref "U$9") (pin "+") (pinfunction "VCC_+") (pintype "bidirectional"))
      (node (ref "U1") (pin "1") (pinfunction "VIN+_1") (pintype "bidirectional"))
    )
    (net (code "47") (name "VIN-") (class "Default")
      (node (ref "D1") (pin "3") (pinfunction "C_3") (pintype "passive"))
      (node (ref "Q1") (pin "3") (pinfunction "S_3") (pintype "passive"))
      (node (ref "R17") (pin "2") (pinfunction "2_2") (pintype "passive"))
      (node (ref "R5") (pin "1") (pinfunction "1_1") (pintype "passive"))
      (node (ref "U1") (pin "2") (pinfunction "VIN-_2") (pintype "bidirectional"))
    )
    (net (code "48") (name "unconnected-(J1-1-Pad8)") (class "Default")
      (node (ref "J1") (pin "8") (pinfunction "1_8") (pintype "passive"))
    )
    (net (code "49") (name "unconnected-(J1-2-Pad7)") (class "Default")
      (node (ref "J1") (pin "7") (pinfunction "2_7") (pintype "passive"))
    )
    (net (code "50") (name "unconnected-(J1-3-Pad6)") (class "Default")
      (node (ref "J1") (pin "6") (pinfunction "3_6") (pintype "passive"))
    )
    (net (code "51") (name "unconnected-(J1-4-Pad5)") (class "Default")
      (node (ref "J1") (pin "5") (pinfunction "4_5") (pintype "passive"))
    )
    (net (code "52") (name "unconnected-(J1-5-Pad4)") (class "Default")
      (node (ref "J1") (pin "4") (pinfunction "5_4") (pintype "passive"))
    )
    (net (code "53") (name "unconnected-(J1-6-Pad3)") (class "Default")
      (node (ref "J1") (pin "3") (pinfunction "6_3") (pintype "passive"))
    )
    (net (code "54") (name "unconnected-(J1-9-Pad15)") (class "Default")
      (node (ref "J1") (pin "15") (pinfunction "9_15") (pintype "passive"))
    )
    (net (code "55") (name "unconnected-(J1-10-Pad14)") (class "Default")
      (node (ref "J1") (pin "14") (pinfunction "10_14") (pintype "passive"))
    )
    (net (code "56") (name "unconnected-(J1-11-Pad13)") (class "Default")
      (node (ref "J1") (pin "13") (pinfunction "11_13") (pintype "passive"))
    )
    (net (code "57") (name "unconnected-(J1-13-Pad11)") (class "Default")
      (node (ref "J1") (pin "11") (pinfunction "13_11") (pintype "passive"))
    )
    (net (code "58") (name "unconnected-(J1-Pad12)") (class "Default")
      (node (ref "J1") (pin "12") (pinfunction "12_12") (pintype "passive"))
    )
    (net (code "59") (name "unconnected-(J1-PadMH1)") (class "Default")
      (node (ref "J1") (pin "MH1") (pinfunction "MH1_MH1") (pintype "passive"))
    )
    (net (code "60") (name "unconnected-(J1-PadMH2)") (class "Default")
      (node (ref "J1") (pin "MH2") (pinfunction "MH2_MH2") (pintype "passive"))
    )
    (net (code "61") (name "unconnected-(J4-Pad17)") (class "Default")
      (node (ref "J4") (pin "17") (pinfunction "17_17") (pintype "passive"))
    )
    (net (code "62") (name "unconnected-(J4-Pad18)") (class "Default")
      (node (ref "J4") (pin "18") (pinfunction "18_18") (pintype "passive"))
    )
    (net (code "63") (name "unconnected-(J4-Pad19)") (class "Default")
      (node (ref "J4") (pin "19") (pinfunction "19_19") (pintype "passive"))
    )
    (net (code "64") (name "unconnected-(J4-Pad22)") (class "Default")
      (node (ref "J4") (pin "22") (pinfunction "22_22") (pintype "passive"))
    )
    (net (code "65") (name "unconnected-(J5-Pad2)") (class "Default")
      (node (ref "J5") (pin "2") (pinfunction "2_2") (pintype "passive"))
    )
    (net (code "66") (name "unconnected-(J5-Pad4)") (class "Default")
      (node (ref "J5") (pin "4") (pinfunction "4_4") (pintype "passive"))
    )
    (net (code "67") (name "unconnected-(J6-Pad2)") (class "Default")
      (node (ref "J6") (pin "2") (pinfunction "2_2") (pintype "passive"))
    )
    (net (code "68") (name "unconnected-(J6-Pad4)") (class "Default")
      (node (ref "J6") (pin "4") (pinfunction "4_4") (pintype "passive"))
    )
    (net (code "69") (name "unconnected-(J6-Pad5)") (class "Default")
      (node (ref "J6") (pin "5") (pinfunction "5_5") (pintype "passive"))
    )
    (net (code "70") (name "unconnected-(J6-Pad6)") (class "Default")
      (node (ref "J6") (pin "6") (pinfunction "6_6") (pintype "passive"))
    )
    (net (code "71") (name "unconnected-(J6-Pad7)") (class "Default")
      (node (ref "J6") (pin "7") (pinfunction "7_7") (pintype "passive"))
    )
    (net (code "72") (name "unconnected-(J6-Pad8)") (class "Default")
      (node (ref "J6") (pin "8") (pinfunction "8_8") (pintype "passive"))
    )
    (net (code "73") (name "unconnected-(J6-Pad10)") (class "Default")
      (node (ref "J6") (pin "10") (pinfunction "10_10") (pintype "passive"))
    )
    (net (code "74") (name "unconnected-(J6-Pad12)") (class "Default")
      (node (ref "J6") (pin "12") (pinfunction "12_12") (pintype "passive"))
    )
    (net (code "75") (name "unconnected-(J6-Pad14)") (class "Default")
      (node (ref "J6") (pin "14") (pinfunction "14_14") (pintype "passive"))
    )
    (net (code "76") (name "unconnected-(J6-Pad16)") (class "Default")
      (node (ref "J6") (pin "16") (pinfunction "16_16") (pintype "passive"))
    )
    (net (code "77") (name "unconnected-(J7-Pad5)") (class "Default")
      (node (ref "J7") (pin "5") (pinfunction "5_5") (pintype "passive"))
    )
    (net (code "78") (name "unconnected-(J7-Pad6)") (class "Default")
      (node (ref "J7") (pin "6") (pinfunction "6_6") (pintype "passive"))
    )
    (net (code "79") (name "unconnected-(J7-Pad7)") (class "Default")
      (node (ref "J7") (pin "7") (pinfunction "7_7") (pintype "passive"))
    )
    (net (code "80") (name "unconnected-(J7-Pad8)") (class "Default")
      (node (ref "J7") (pin "8") (pinfunction "8_8") (pintype "passive"))
    )
    (net (code "81") (name "unconnected-(J8-Pad6)") (class "Default")
      (node (ref "J8") (pin "6") (pinfunction "6_6") (pintype "passive"))
    )
    (net (code "82") (name "unconnected-(J8-Pad8)") (class "Default")
      (node (ref "J8") (pin "8") (pinfunction "8_8") (pintype "passive"))
    )
    (net (code "83") (name "unconnected-(J8-Pad10)") (class "Default")
      (node (ref "J8") (pin "10") (pinfunction "10_10") (pintype "passive"))
    )
    (net (code "84") (name "unconnected-(J8-Pad12)") (class "Default")
      (node (ref "J8") (pin "12") (pinfunction "12_12") (pintype "passive"))
    )
    (net (code "85") (name "unconnected-(J8-Pad14)") (class "Default")
      (node (ref "J8") (pin "14") (pinfunction "14_14") (pintype "passive"))
    )
    (net (code "86") (name "unconnected-(J8-Pad16)") (class "Default")
      (node (ref "J8") (pin "16") (pinfunction "16_16") (pintype "passive"))
    )
    (net (code "87") (name "unconnected-(PAD1-P-Pad1)") (class "Default")
      (node (ref "PAD1") (pin "1") (pinfunction "P_1") (pintype "passive"))
    )
    (net (code "88") (name "unconnected-(PAD2-P-Pad1)") (class "Default")
      (node (ref "PAD2") (pin "1") (pinfunction "P_1") (pintype "passive"))
    )
    (net (code "89") (name "unconnected-(PAD3-P-Pad1)") (class "Default")
      (node (ref "PAD3") (pin "1") (pinfunction "P_1") (pintype "passive"))
    )
    (net (code "90") (name "unconnected-(PAD4-P-Pad1)") (class "Default")
      (node (ref "PAD4") (pin "1") (pinfunction "P_1") (pintype "passive"))
    )
    (net (code "91") (name "unconnected-(PAD5-P-Pad1)") (class "Default")
      (node (ref "PAD5") (pin "1") (pinfunction "P_1") (pintype "passive"))
    )
    (net (code "92") (name "unconnected-(PAD6-P-Pad1)") (class "Default")
      (node (ref "PAD6") (pin "1") (pinfunction "P_1") (pintype "passive"))
    )
    (net (code "93") (name "unconnected-(PAD7-P-Pad1)") (class "Default")
      (node (ref "PAD7") (pin "1") (pinfunction "P_1") (pintype "passive"))
    )
    (net (code "94") (name "unconnected-(PAD8-P-Pad1)") (class "Default")
      (node (ref "PAD8") (pin "1") (pinfunction "P_1") (pintype "passive"))
    )
    (net (code "95") (name "unconnected-(PAD9-P-Pad1)") (class "Default")
      (node (ref "PAD9") (pin "1") (pinfunction "P_1") (pintype "passive"))
    )
    (net (code "96") (name "unconnected-(PAD10-P-Pad1)") (class "Default")
      (node (ref "PAD10") (pin "1") (pinfunction "P_1") (pintype "passive"))
    )
    (net (code "97") (name "unconnected-(PAD11-P-Pad1)") (class "Default")
      (node (ref "PAD11") (pin "1") (pinfunction "P_1") (pintype "passive"))
    )
    (net (code "98") (name "unconnected-(PAD12-P-Pad1)") (class "Default")
      (node (ref "PAD12") (pin "1") (pinfunction "P_1") (pintype "passive"))
    )
    (net (code "99") (name "unconnected-(PAD13-P-Pad1)") (class "Default")
      (node (ref "PAD13") (pin "1") (pinfunction "P_1") (pintype "passive"))
    )
    (net (code "100") (name "unconnected-(PAD14-P-Pad1)") (class "Default")
      (node (ref "PAD14") (pin "1") (pinfunction "P_1") (pintype "passive"))
    )
    (net (code "101") (name "unconnected-(PAD15-P-Pad1)") (class "Default")
      (node (ref "PAD15") (pin "1") (pinfunction "P_1") (pintype "passive"))
    )
    (net (code "102") (name "unconnected-(PAD16-P-Pad1)") (class "Default")
      (node (ref "PAD16") (pin "1") (pinfunction "P_1") (pintype "passive"))
    )
    (net (code "103") (name "unconnected-(PAD17-P-Pad1)") (class "Default")
      (node (ref "PAD17") (pin "1") (pinfunction "P_1") (pintype "passive"))
    )
    (net (code "104") (name "unconnected-(PAD18-P-Pad1)") (class "Default")
      (node (ref "PAD18") (pin "1") (pinfunction "P_1") (pintype "passive"))
    )
    (net (code "105") (name "unconnected-(PAD19-P-Pad1)") (class "Default")
      (node (ref "PAD19") (pin "1") (pinfunction "P_1") (pintype "passive"))
    )
    (net (code "106") (name "unconnected-(PAD20-P-Pad1)") (class "Default")
      (node (ref "PAD20") (pin "1") (pinfunction "P_1") (pintype "passive"))
    )
    (net (code "107") (name "unconnected-(PAD21-P-Pad1)") (class "Default")
      (node (ref "PAD21") (pin "1") (pinfunction "P_1") (pintype "passive"))
    )
    (net (code "108") (name "unconnected-(PAD22-P-Pad1)") (class "Default")
      (node (ref "PAD22") (pin "1") (pinfunction "P_1") (pintype "passive"))
    )
    (net (code "109") (name "unconnected-(PAD23-P-Pad1)") (class "Default")
      (node (ref "PAD23") (pin "1") (pinfunction "P_1") (pintype "passive"))
    )
    (net (code "110") (name "unconnected-(PAD24-P-Pad1)") (class "Default")
      (node (ref "PAD24") (pin "1") (pinfunction "P_1") (pintype "passive"))
    )
    (net (code "111") (name "unconnected-(PAD25-P-Pad1)") (class "Default")
      (node (ref "PAD25") (pin "1") (pinfunction "P_1") (pintype "passive"))
    )
    (net (code "112") (name "unconnected-(PAD26-P-Pad1)") (class "Default")
      (node (ref "PAD26") (pin "1") (pinfunction "P_1") (pintype "passive"))
    )
    (net (code "113") (name "unconnected-(PAD27-P-Pad1)") (class "Default")
      (node (ref "PAD27") (pin "1") (pinfunction "P_1") (pintype "passive"))
    )
    (net (code "114") (name "unconnected-(PAD28-P-Pad1)") (class "Default")
      (node (ref "PAD28") (pin "1") (pinfunction "P_1") (pintype "passive"))
    )
    (net (code "115") (name "unconnected-(PAD29-P-Pad1)") (class "Default")
      (node (ref "PAD29") (pin "1") (pinfunction "P_1") (pintype "passive"))
    )
    (net (code "116") (name "unconnected-(PAD30-P-Pad1)") (class "Default")
      (node (ref "PAD30") (pin "1") (pinfunction "P_1") (pintype "passive"))
    )
    (net (code "117") (name "unconnected-(PAD31-P-Pad1)") (class "Default")
      (node (ref "PAD31") (pin "1") (pinfunction "P_1") (pintype "passive"))
    )
    (net (code "118") (name "unconnected-(PAD32-P-Pad1)") (class "Default")
      (node (ref "PAD32") (pin "1") (pinfunction "P_1") (pintype "passive"))
    )
    (net (code "119") (name "unconnected-(PAD33-P-Pad1)") (class "Default")
      (node (ref "PAD33") (pin "1") (pinfunction "P_1") (pintype "passive"))
    )
    (net (code "120") (name "unconnected-(PAD34-P-Pad1)") (class "Default")
      (node (ref "PAD34") (pin "1") (pinfunction "P_1") (pintype "passive"))
    )
    (net (code "121") (name "unconnected-(PAD35-P-Pad1)") (class "Default")
      (node (ref "PAD35") (pin "1") (pinfunction "P_1") (pintype "passive"))
    )
    (net (code "122") (name "unconnected-(PAD36-P-Pad1)") (class "Default")
      (node (ref "PAD36") (pin "1") (pinfunction "P_1") (pintype "passive"))
    )
    (net (code "123") (name "unconnected-(PAD37-P-Pad1)") (class "Default")
      (node (ref "PAD37") (pin "1") (pinfunction "P_1") (pintype "passive"))
    )
    (net (code "124") (name "unconnected-(PAD38-P-Pad1)") (class "Default")
      (node (ref "PAD38") (pin "1") (pinfunction "P_1") (pintype "passive"))
    )
    (net (code "125") (name "unconnected-(PAD39-P-Pad1)") (class "Default")
      (node (ref "PAD39") (pin "1") (pinfunction "P_1") (pintype "passive"))
    )
    (net (code "126") (name "unconnected-(PAD41-P-Pad1)") (class "Default")
      (node (ref "PAD41") (pin "1") (pinfunction "P_1") (pintype "passive"))
    )
    (net (code "127") (name "unconnected-(PAD43-P-Pad1)") (class "Default")
      (node (ref "PAD43") (pin "1") (pinfunction "P_1") (pintype "passive"))
    )
    (net (code "128") (name "unconnected-(PAD45-P-Pad1)") (class "Default")
      (node (ref "PAD45") (pin "1") (pinfunction "P_1") (pintype "passive"))
    )
    (net (code "129") (name "unconnected-(S1-O-Pad1)") (class "Default")
      (node (ref "S1") (pin "1") (pinfunction "O_1") (pintype "passive"))
    )
  )
)
